# cylonite.net
KiCad netlist of a schematic drawn in EAGLE
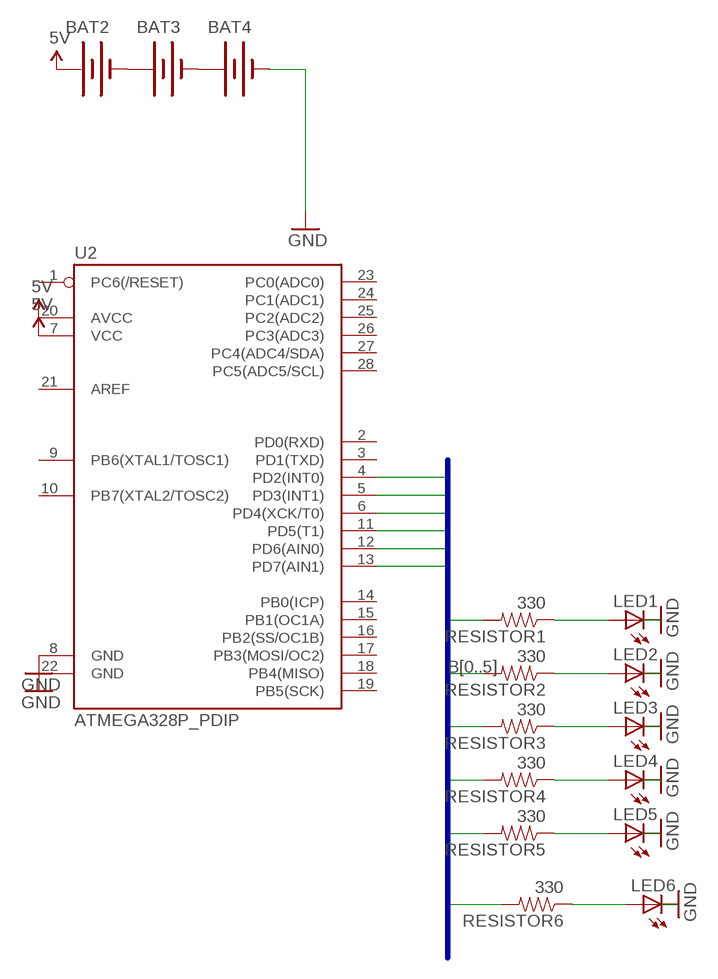
[diagram p0: schematic, sheet 1]

(export (version "E")
  (design (tool "Eeschema 10.0.6"))
  (components
    (comp (ref "BAT2")
      (value "BATTERYAA")
      (footprint "eagle-import:BATTERY-AA")
      (libsource (lib "eagle-import") (part "BATTERYAA"))
    )
    (comp (ref "BAT3")
      (value "BATTERYAA")
      (footprint "eagle-import:BATTERY-AA")
      (libsource (lib "eagle-import") (part "BATTERYAA"))
    )
    (comp (ref "BAT4")
      (value "BATTERYAA")
      (footprint "eagle-import:BATTERY-AA")
      (libsource (lib "eagle-import") (part "BATTERYAA"))
    )
    (comp (ref "LED1")
      (value "LED5MM")
      (footprint "eagle-import:LED5MM")
      (libsource (lib "eagle-import") (part "LED5MM"))
    )
    (comp (ref "LED2")
      (value "LED5MM")
      (footprint "eagle-import:LED5MM")
      (libsource (lib "eagle-import") (part "LED5MM"))
    )
    (comp (ref "LED3")
      (value "LED5MM")
      (footprint "eagle-import:LED5MM")
      (libsource (lib "eagle-import") (part "LED5MM"))
    )
    (comp (ref "LED4")
      (value "LED5MM")
      (footprint "eagle-import:LED5MM")
      (libsource (lib "eagle-import") (part "LED5MM"))
    )
    (comp (ref "LED5")
      (value "LED5MM")
      (footprint "eagle-import:LED5MM")
      (libsource (lib "eagle-import") (part "LED5MM"))
    )
    (comp (ref "LED6")
      (value "LED5MM")
      (footprint "eagle-import:LED5MM")
      (libsource (lib "eagle-import") (part "LED5MM"))
    )
    (comp (ref "RESISTOR1")
      (value "330")
      (footprint "eagle-import:AXIAL-0.4")
      (libsource (lib "eagle-import") (part "RESISTORPTH-1/4W"))
    )
    (comp (ref "RESISTOR2")
      (value "330")
      (footprint "eagle-import:AXIAL-0.4")
      (libsource (lib "eagle-import") (part "RESISTORPTH-1/4W"))
    )
    (comp (ref "RESISTOR3")
      (value "330")
      (footprint "eagle-import:AXIAL-0.4")
      (libsource (lib "eagle-import") (part "RESISTORPTH-1/4W"))
    )
    (comp (ref "RESISTOR4")
      (value "330")
      (footprint "eagle-import:AXIAL-0.4")
      (libsource (lib "eagle-import") (part "RESISTORPTH-1/4W"))
    )
    (comp (ref "RESISTOR5")
      (value "330")
      (footprint "eagle-import:AXIAL-0.4")
      (libsource (lib "eagle-import") (part "RESISTORPTH-1/4W"))
    )
    (comp (ref "RESISTOR6")
      (value "330")
      (footprint "eagle-import:AXIAL-0.4")
      (libsource (lib "eagle-import") (part "RESISTORPTH-1/4W"))
    )
    (comp (ref "U2")
      (value "ATMEGA328P_PDIP")
      (footprint "eagle-import:DIL28-3")
      (libsource (lib "eagle-import") (part "ATMEGA328P_PDIP"))
    )
  )
  (nets
    (net (code "1") (name "/B0") (class "Default")
      (node (ref "RESISTOR1") (pin "P$2") (pinfunction "2_P$2") (pintype "passive"))
      (node (ref "U2") (pin "4") (pinfunction "PD2(INT0)_4") (pintype "bidirectional"))
    )
    (net (code "2") (name "/B1") (class "Default")
      (node (ref "RESISTOR2") (pin "P$2") (pinfunction "2_P$2") (pintype "passive"))
      (node (ref "U2") (pin "5") (pinfunction "PD3(INT1)_5") (pintype "bidirectional"))
    )
    (net (code "3") (name "/B2") (class "Default")
      (node (ref "RESISTOR3") (pin "P$2") (pinfunction "2_P$2") (pintype "passive"))
      (node (ref "U2") (pin "6") (pinfunction "PD4(XCK/T0)_6") (pintype "bidirectional"))
    )
    (net (code "4") (name "/B3") (class "Default")
      (node (ref "RESISTOR4") (pin "P$2") (pinfunction "2_P$2") (pintype "passive"))
      (node (ref "U2") (pin "11") (pinfunction "PD5(T1)_11") (pintype "bidirectional"))
    )
    (net (code "5") (name "/B4") (class "Default")
      (node (ref "RESISTOR5") (pin "P$2") (pinfunction "2_P$2") (pintype "passive"))
      (node (ref "U2") (pin "12") (pinfunction "PD6(AIN0)_12") (pintype "bidirectional"))
    )
    (net (code "6") (name "/B5") (class "Default")
      (node (ref "RESISTOR6") (pin "P$2") (pinfunction "2_P$2") (pintype "passive"))
      (node (ref "U2") (pin "13") (pinfunction "PD7(AIN1)_13") (pintype "bidirectional"))
    )
    (net (code "8") (name "5V") (class "Default")
      (node (ref "BAT2") (pin "PWR@1") (pinfunction "+_PWR@1") (pintype "power_in"))
      (node (ref "U2") (pin "20") (pinfunction "AVCC_20") (pintype "bidirectional"))
      (node (ref "U2") (pin "7") (pinfunction "VCC_7") (pintype "bidirectional"))
    )
    (net (code "9") (name "GND") (class "Default")
      (node (ref "BAT4") (pin "GND@1") (pinfunction "-_GND@1") (pintype "power_in"))
      (node (ref "LED1") (pin "K") (pinfunction "C_K") (pintype "passive"))
      (node (ref "LED2") (pin "K") (pinfunction "C_K") (pintype "passive"))
      (node (ref "LED3") (pin "K") (pinfunction "C_K") (pintype "passive"))
      (node (ref "LED4") (pin "K") (pinfunction "C_K") (pintype "passive"))
      (node (ref "LED5") (pin "K") (pinfunction "C_K") (pintype "passive"))
      (node (ref "LED6") (pin "K") (pinfunction "C_K") (pintype "passive"))
      (node (ref "U2") (pin "22") (pinfunction "GND_22") (pintype "bidirectional"))
      (node (ref "U2") (pin "8") (pinfunction "GND_8") (pintype "bidirectional"))
    )
    (net (code "10") (name "Net-(BAT2--)") (class "Default")
      (node (ref "BAT2") (pin "GND@1") (pinfunction "-_GND@1") (pintype "power_in"))
      (node (ref "BAT3") (pin "PWR@1") (pinfunction "+_PWR@1") (pintype "power_in"))
    )
    (net (code "11") (name "Net-(BAT3--)") (class "Default")
      (node (ref "BAT3") (pin "GND@1") (pinfunction "-_GND@1") (pintype "power_in"))
      (node (ref "BAT4") (pin "PWR@1") (pinfunction "+_PWR@1") (pintype "power_in"))
    )
    (net (code "12") (name "Net-(RESISTOR1-1)") (class "Default")
      (node (ref "LED1") (pin "A") (pinfunction "A_A") (pintype "passive"))
      (node (ref "RESISTOR1") (pin "P$1") (pinfunction "1_P$1") (pintype "passive"))
    )
    (net (code "13") (name "Net-(RESISTOR2-1)") (class "Default")
      (node (ref "LED2") (pin "A") (pinfunction "A_A") (pintype "passive"))
      (node (ref "RESISTOR2") (pin "P$1") (pinfunction "1_P$1") (pintype "passive"))
    )
    (net (code "14") (name "Net-(RESISTOR3-1)") (class "Default")
      (node (ref "LED3") (pin "A") (pinfunction "A_A") (pintype "passive"))
      (node (ref "RESISTOR3") (pin "P$1") (pinfunction "1_P$1") (pintype "passive"))
    )
    (net (code "15") (name "Net-(RESISTOR4-1)") (class "Default")
      (node (ref "LED4") (pin "A") (pinfunction "A_A") (pintype "passive"))
      (node (ref "RESISTOR4") (pin "P$1") (pinfunction "1_P$1") (pintype "passive"))
    )
    (net (code "16") (name "Net-(RESISTOR5-1)") (class "Default")
      (node (ref "LED5") (pin "A") (pinfunction "A_A") (pintype "passive"))
      (node (ref "RESISTOR5") (pin "P$1") (pinfunction "1_P$1") (pintype "passive"))
    )
    (net (code "17") (name "Net-(RESISTOR6-1)") (class "Default")
      (node (ref "LED6") (pin "A") (pinfunction "A_A") (pintype "passive"))
      (node (ref "RESISTOR6") (pin "P$1") (pinfunction "1_P$1") (pintype "passive"))
    )
    (net (code "18") (name "unconnected-(U2-AREF-Pad21)") (class "Default")
      (node (ref "U2") (pin "21") (pinfunction "AREF_21") (pintype "bidirectional"))
    )
    (net (code "19") (name "unconnected-(U2-PB0(ICP)-Pad14)") (class "Default")
      (node (ref "U2") (pin "14") (pinfunction "PB0(ICP)_14") (pintype "bidirectional"))
    )
    (net (code "20") (name "unconnected-(U2-PB1(OC1A)-Pad15)") (class "Default")
      (node (ref "U2") (pin "15") (pinfunction "PB1(OC1A)_15") (pintype "bidirectional"))
    )
    (net (code "21") (name "unconnected-(U2-PB2(SS{slash}OC1B)-Pad16)") (class "Default")
      (node (ref "U2") (pin "16") (pinfunction "PB2(SS/OC1B)_16") (pintype "bidirectional"))
    )
    (net (code "22") (name "unconnected-(U2-PB3(MOSI{slash}OC2)-Pad17)") (class "Default")
      (node (ref "U2") (pin "17") (pinfunction "PB3(MOSI/OC2)_17") (pintype "bidirectional"))
    )
    (net (code "23") (name "unconnected-(U2-PB4(MISO)-Pad18)") (class "Default")
      (node (ref "U2") (pin "18") (pinfunction "PB4(MISO)_18") (pintype "bidirectional"))
    )
    (net (code "24") (name "unconnected-(U2-PB5(SCK)-Pad19)") (class "Default")
      (node (ref "U2") (pin "19") (pinfunction "PB5(SCK)_19") (pintype "bidirectional"))
    )
    (net (code "25") (name "unconnected-(U2-PB6(XTAL1{slash}TOSC1)-Pad9)") (class "Default")
      (node (ref "U2") (pin "9") (pinfunction "PB6(XTAL1/TOSC1)_9") (pintype "bidirectional"))
    )
    (net (code "26") (name "unconnected-(U2-PB7(XTAL2{slash}TOSC2)-Pad10)") (class "Default")
      (node (ref "U2") (pin "10") (pinfunction "PB7(XTAL2/TOSC2)_10") (pintype "bidirectional"))
    )
    (net (code "27") (name "unconnected-(U2-PC0(ADC0)-Pad23)") (class "Default")
      (node (ref "U2") (pin "23") (pinfunction "PC0(ADC0)_23") (pintype "bidirectional"))
    )
    (net (code "28") (name "unconnected-(U2-PC1(ADC1)-Pad24)") (class "Default")
      (node (ref "U2") (pin "24") (pinfunction "PC1(ADC1)_24") (pintype "bidirectional"))
    )
    (net (code "29") (name "unconnected-(U2-PC2(ADC2)-Pad25)") (class "Default")
      (node (ref "U2") (pin "25") (pinfunction "PC2(ADC2)_25") (pintype "bidirectional"))
    )
    (net (code "30") (name "unconnected-(U2-PC3(ADC3)-Pad26)") (class "Default")
      (node (ref "U2") (pin "26") (pinfunction "PC3(ADC3)_26") (pintype "bidirectional"))
    )
    (net (code "31") (name "unconnected-(U2-PC4(ADC4{slash}SDA)-Pad27)") (class "Default")
      (node (ref "U2") (pin "27") (pinfunction "PC4(ADC4/SDA)_27") (pintype "bidirectional"))
    )
    (net (code "32") (name "unconnected-(U2-PC5(ADC5{slash}SCL)-Pad28)") (class "Default")
      (node (ref "U2") (pin "28") (pinfunction "PC5(ADC5/SCL)_28") (pintype "bidirectional"))
    )
    (net (code "33") (name "unconnected-(U2-PC6({slash}RESET)-Pad1)") (class "Default")
      (node (ref "U2") (pin "1") (pinfunction "PC6(/RESET)_1") (pintype "bidirectional"))
    )
    (net (code "34") (name "unconnected-(U2-PD0(RXD)-Pad2)") (class "Default")
      (node (ref "U2") (pin "2") (pinfunction "PD0(RXD)_2") (pintype "bidirectional"))
    )
    (net (code "35") (name "unconnected-(U2-PD1(TXD)-Pad3)") (class "Default")
      (node (ref "U2") (pin "3") (pinfunction "PD1(TXD)_3") (pintype "bidirectional"))
    )
  )
)
